# main_board.net
KiCad netlist of a schematic drawn in EAGLE
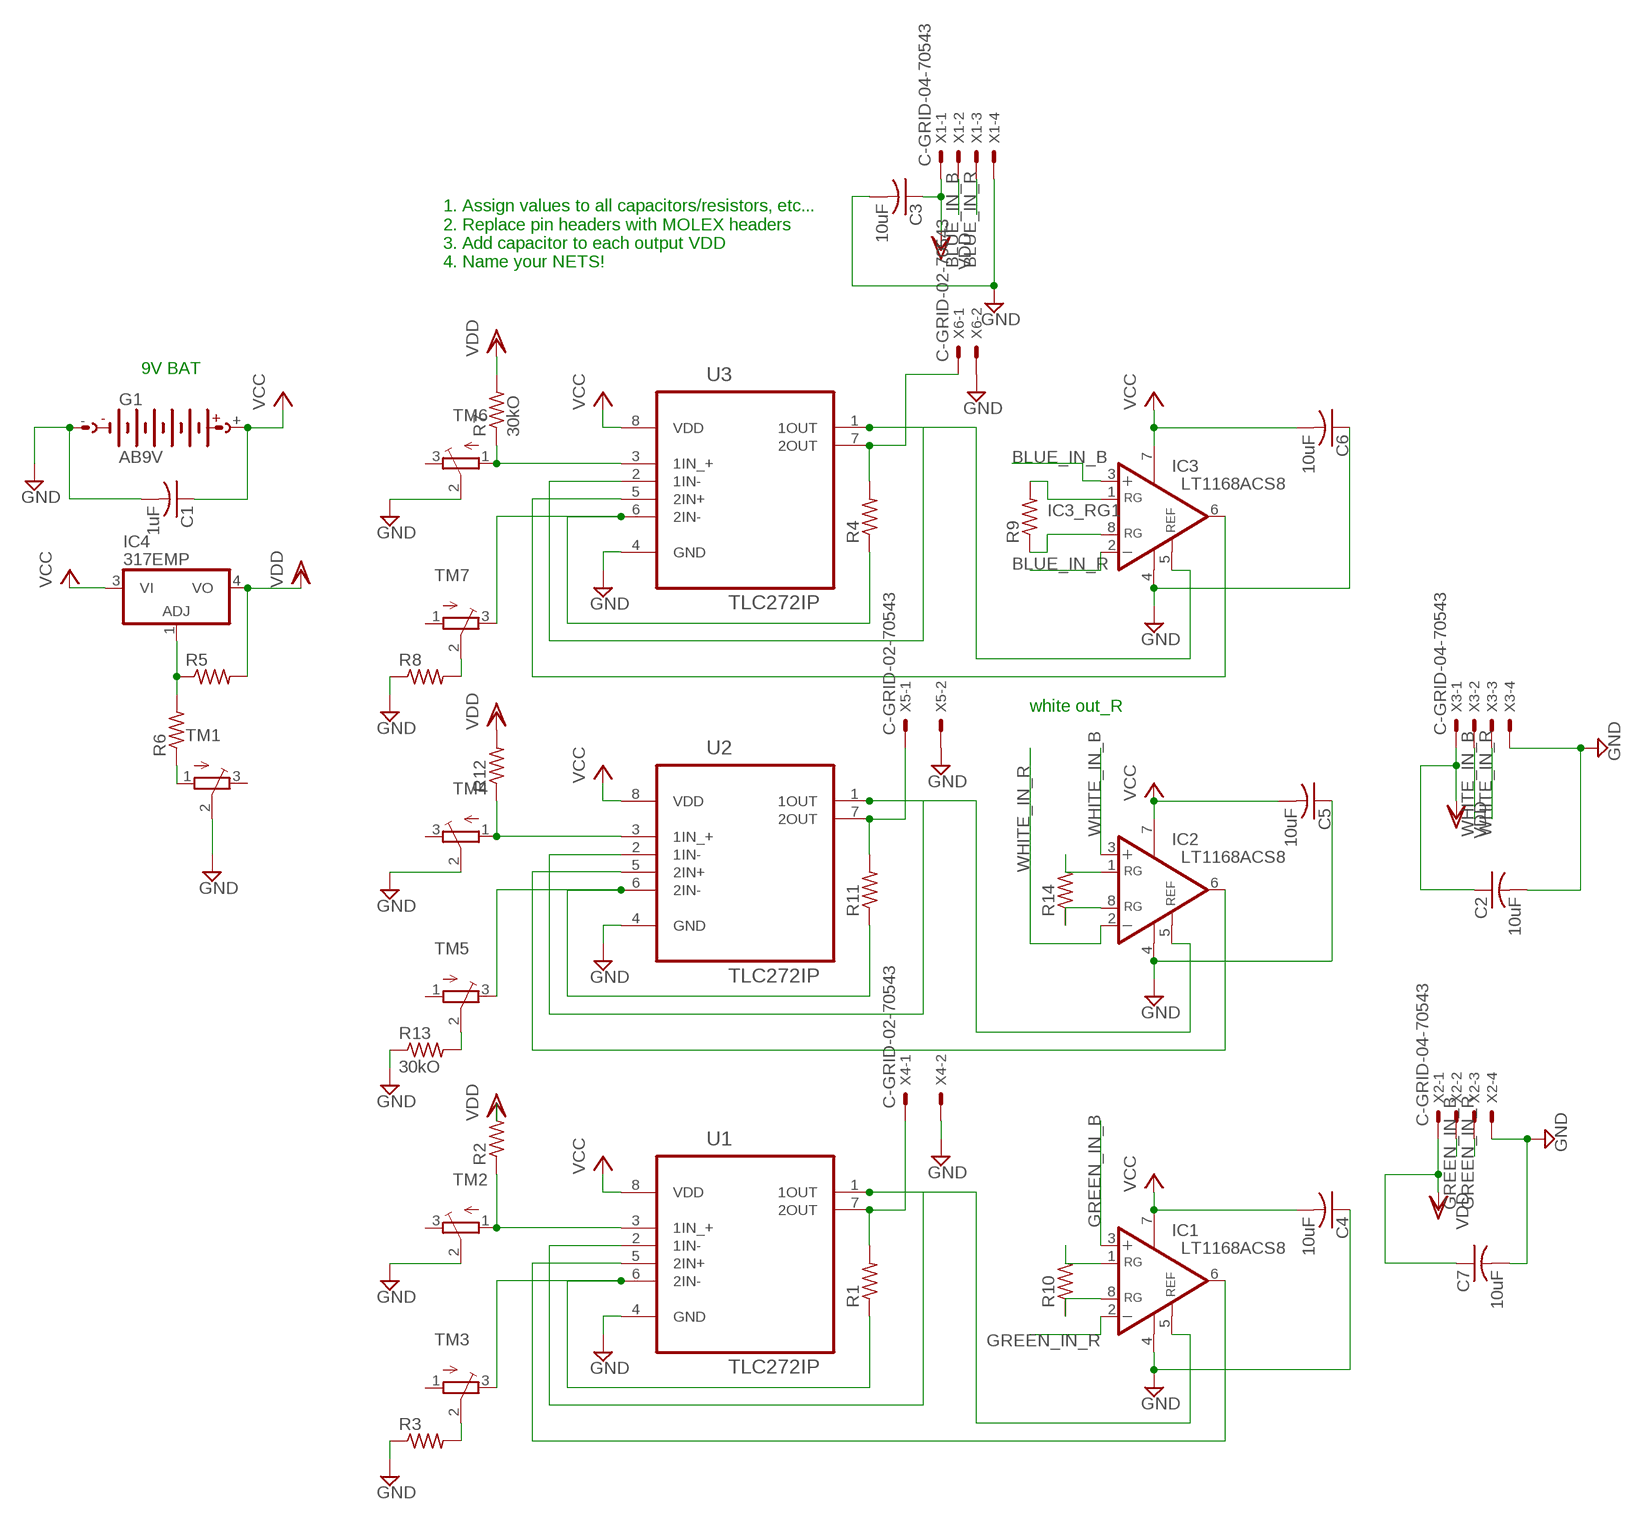
[diagram p0: schematic, sheet 1]

(export (version "E")
  (design (tool "Eeschema 10.0.6"))
  (components
    (comp (ref "C1")
      (value "1uF")
      (footprint "eagle-import:C2012")
      (libsource (lib "eagle-import") (part "C-USC2012"))
    )
    (comp (ref "C2")
      (value "10uF")
      (footprint "eagle-import:C2012")
      (libsource (lib "eagle-import") (part "C-USC2012"))
    )
    (comp (ref "C3")
      (value "10uF")
      (footprint "eagle-import:C2012")
      (libsource (lib "eagle-import") (part "C-USC2012"))
    )
    (comp (ref "C4")
      (value "10uF")
      (footprint "eagle-import:C2012")
      (libsource (lib "eagle-import") (part "C-USC2012"))
    )
    (comp (ref "C5")
      (value "10uF")
      (footprint "eagle-import:C2012")
      (libsource (lib "eagle-import") (part "C-USC2012"))
    )
    (comp (ref "C6")
      (value "10uF")
      (footprint "eagle-import:C2012")
      (libsource (lib "eagle-import") (part "C-USC2012"))
    )
    (comp (ref "C7")
      (value "10uF")
      (footprint "eagle-import:C2012")
      (libsource (lib "eagle-import") (part "C-USC2012"))
    )
    (comp (ref "G1")
      (value "AB9V")
      (footprint "eagle-import:AB9V")
      (libsource (lib "eagle-import") (part "AB9V"))
    )
    (comp (ref "IC1")
      (value "LT1168ACS8")
      (footprint "eagle-import:SOIC8")
      (libsource (lib "eagle-import") (part "LT1168S8AC"))
    )
    (comp (ref "IC2")
      (value "LT1168ACS8")
      (footprint "eagle-import:SOIC8")
      (libsource (lib "eagle-import") (part "LT1168S8AC"))
    )
    (comp (ref "IC3")
      (value "LT1168ACS8")
      (footprint "eagle-import:SOIC8")
      (libsource (lib "eagle-import") (part "LT1168S8AC"))
    )
    (comp (ref "IC4")
      (value "317EMP")
      (footprint "eagle-import:SOT223")
      (libsource (lib "eagle-import") (part "317EMP"))
    )
    (comp (ref "R1")
      (value "R-US_R1206")
      (footprint "eagle-import:R1206")
      (libsource (lib "eagle-import") (part "R-US_R1206"))
    )
    (comp (ref "R2")
      (value "R-US_R1206")
      (footprint "eagle-import:R1206")
      (libsource (lib "eagle-import") (part "R-US_R1206"))
    )
    (comp (ref "R3")
      (value "R-US_R1206")
      (footprint "eagle-import:R1206")
      (libsource (lib "eagle-import") (part "R-US_R1206"))
    )
    (comp (ref "R4")
      (value "R-US_R1206")
      (footprint "eagle-import:R1206")
      (libsource (lib "eagle-import") (part "R-US_R1206"))
    )
    (comp (ref "R5")
      (value "R-US_R1206")
      (footprint "eagle-import:R1206")
      (libsource (lib "eagle-import") (part "R-US_R1206"))
    )
    (comp (ref "R6")
      (value "R-US_R1206")
      (footprint "eagle-import:R1206")
      (libsource (lib "eagle-import") (part "R-US_R1206"))
    )
    (comp (ref "R7")
      (value "30kO")
      (footprint "eagle-import:R1206")
      (libsource (lib "eagle-import") (part "R-US_R1206"))
    )
    (comp (ref "R8")
      (value "R-US_R1206")
      (footprint "eagle-import:R1206")
      (libsource (lib "eagle-import") (part "R-US_R1206"))
    )
    (comp (ref "R9")
      (value "R-US_R1206")
      (footprint "eagle-import:R1206")
      (libsource (lib "eagle-import") (part "R-US_R1206"))
    )
    (comp (ref "R10")
      (value "R-US_R1206")
      (footprint "eagle-import:R1206")
      (libsource (lib "eagle-import") (part "R-US_R1206"))
    )
    (comp (ref "R11")
      (value "R-US_R1206")
      (footprint "eagle-import:R1206")
      (libsource (lib "eagle-import") (part "R-US_R1206"))
    )
    (comp (ref "R12")
      (value "R-US_R1206")
      (footprint "eagle-import:R1206")
      (libsource (lib "eagle-import") (part "R-US_R1206"))
    )
    (comp (ref "R13")
      (value "30kO")
      (footprint "eagle-import:R1206")
      (libsource (lib "eagle-import") (part "R-US_R1206"))
    )
    (comp (ref "R14")
      (value "R-US_R1206")
      (footprint "eagle-import:R1206")
      (libsource (lib "eagle-import") (part "R-US_R1206"))
    )
    (comp (ref "TM1")
      (value "TRIMPOT3386")
      (footprint "eagle-import:TRIM-3386")
      (libsource (lib "eagle-import") (part "TRIMPOT3386"))
    )
    (comp (ref "TM2")
      (value "TRIMPOT3386")
      (footprint "eagle-import:TRIM-3386")
      (libsource (lib "eagle-import") (part "TRIMPOT3386"))
    )
    (comp (ref "TM3")
      (value "TRIMPOT3386")
      (footprint "eagle-import:TRIM-3386")
      (libsource (lib "eagle-import") (part "TRIMPOT3386"))
    )
    (comp (ref "TM4")
      (value "TRIMPOT3386")
      (footprint "eagle-import:TRIM-3386")
      (libsource (lib "eagle-import") (part "TRIMPOT3386"))
    )
    (comp (ref "TM5")
      (value "TRIMPOT3386")
      (footprint "eagle-import:TRIM-3386")
      (libsource (lib "eagle-import") (part "TRIMPOT3386"))
    )
    (comp (ref "TM6")
      (value "TRIMPOT3386")
      (footprint "eagle-import:TRIM-3386")
      (libsource (lib "eagle-import") (part "TRIMPOT3386"))
    )
    (comp (ref "TM7")
      (value "TRIMPOT3386")
      (footprint "eagle-import:TRIM-3386")
      (libsource (lib "eagle-import") (part "TRIMPOT3386"))
    )
    (comp (ref "U1")
      (value "TLC272IP")
      (footprint "eagle-import:DIP254P762X508-8")
      (libsource (lib "eagle-import") (part "TLC272IP"))
    )
    (comp (ref "U2")
      (value "TLC272IP")
      (footprint "eagle-import:DIP254P762X508-8")
      (libsource (lib "eagle-import") (part "TLC272IP"))
    )
    (comp (ref "U3")
      (value "TLC272IP")
      (footprint "eagle-import:DIP254P762X508-8")
      (libsource (lib "eagle-import") (part "TLC272IP"))
    )
    (comp (ref "X1")
      (value "C-GRID-04-70543")
      (footprint "eagle-import:70543-04")
      (libsource (lib "eagle-import") (part "C-GRID-04-70543"))
    )
    (comp (ref "X2")
      (value "C-GRID-04-70543")
      (footprint "eagle-import:70543-04")
      (libsource (lib "eagle-import") (part "C-GRID-04-70543"))
    )
    (comp (ref "X3")
      (value "C-GRID-04-70543")
      (footprint "eagle-import:70543-04")
      (libsource (lib "eagle-import") (part "C-GRID-04-70543"))
    )
    (comp (ref "X4")
      (value "C-GRID-02-70543")
      (footprint "eagle-import:70543-02")
      (libsource (lib "eagle-import") (part "C-GRID-02-70543"))
    )
    (comp (ref "X5")
      (value "C-GRID-02-70543")
      (footprint "eagle-import:70543-02")
      (libsource (lib "eagle-import") (part "C-GRID-02-70543"))
    )
    (comp (ref "X6")
      (value "C-GRID-02-70543")
      (footprint "eagle-import:70543-02")
      (libsource (lib "eagle-import") (part "C-GRID-02-70543"))
    )
  )
  (nets
    (net (code "1") (name "/BLUE_IN_B") (class "Default")
      (node (ref "IC3") (pin "3") (pinfunction "+IN_3") (pintype "input"))
      (node (ref "X1") (pin "2") (pinfunction "S_2") (pintype "passive"))
    )
    (net (code "2") (name "/BLUE_IN_R") (class "Default")
      (node (ref "IC3") (pin "2") (pinfunction "-IN_2") (pintype "input"))
      (node (ref "X1") (pin "3") (pinfunction "S_3") (pintype "passive"))
    )
    (net (code "3") (name "/GREEN_IN_B") (class "Default")
      (node (ref "IC1") (pin "3") (pinfunction "+IN_3") (pintype "input"))
      (node (ref "X2") (pin "2") (pinfunction "S_2") (pintype "passive"))
    )
    (net (code "4") (name "/GREEN_IN_R") (class "Default")
      (node (ref "IC1") (pin "2") (pinfunction "-IN_2") (pintype "input"))
      (node (ref "X2") (pin "3") (pinfunction "S_3") (pintype "passive"))
    )
    (net (code "5") (name "/IC3_RG1") (class "Default")
      (node (ref "IC3") (pin "1") (pinfunction "RG_1") (pintype "input"))
      (node (ref "R9") (pin "2") (pinfunction "2_2") (pintype "passive"))
    )
    (net (code "6") (name "/WHITE_IN_B") (class "Default")
      (node (ref "IC2") (pin "3") (pinfunction "+IN_3") (pintype "input"))
      (node (ref "X3") (pin "2") (pinfunction "S_2") (pintype "passive"))
    )
    (net (code "7") (name "/WHITE_IN_R") (class "Default")
      (node (ref "IC2") (pin "2") (pinfunction "-IN_2") (pintype "input"))
      (node (ref "X3") (pin "3") (pinfunction "S_3") (pintype "passive"))
    )
    (net (code "8") (name "GND") (class "Default")
      (node (ref "C1") (pin "2") (pinfunction "2_2") (pintype "passive"))
      (node (ref "C2") (pin "2") (pinfunction "2_2") (pintype "passive"))
      (node (ref "C3") (pin "2") (pinfunction "2_2") (pintype "passive"))
      (node (ref "C4") (pin "1") (pinfunction "1_1") (pintype "passive"))
      (node (ref "C5") (pin "1") (pinfunction "1_1") (pintype "passive"))
      (node (ref "C6") (pin "1") (pinfunction "1_1") (pintype "passive"))
      (node (ref "C7") (pin "2") (pinfunction "2_2") (pintype "passive"))
      (node (ref "G1") (pin "-") (pinfunction "-_-") (pintype "passive"))
      (node (ref "IC1") (pin "4") (pinfunction "V-_4") (pintype "power_in"))
      (node (ref "IC2") (pin "4") (pinfunction "V-_4") (pintype "power_in"))
      (node (ref "IC3") (pin "4") (pinfunction "V-_4") (pintype "power_in"))
      (node (ref "R13") (pin "1") (pinfunction "1_1") (pintype "passive"))
      (node (ref "R3") (pin "1") (pinfunction "1_1") (pintype "passive"))
      (node (ref "R8") (pin "1") (pinfunction "1_1") (pintype "passive"))
      (node (ref "TM1") (pin "2") (pinfunction "S_2") (pintype "passive"))
      (node (ref "TM2") (pin "2") (pinfunction "S_2") (pintype "passive"))
      (node (ref "TM4") (pin "2") (pinfunction "S_2") (pintype "passive"))
      (node (ref "TM6") (pin "2") (pinfunction "S_2") (pintype "passive"))
      (node (ref "U1") (pin "4") (pinfunction "GND_4") (pintype "passive"))
      (node (ref "U2") (pin "4") (pinfunction "GND_4") (pintype "passive"))
      (node (ref "U3") (pin "4") (pinfunction "GND_4") (pintype "passive"))
      (node (ref "X1") (pin "4") (pinfunction "S_4") (pintype "passive"))
      (node (ref "X2") (pin "4") (pinfunction "S_4") (pintype "passive"))
      (node (ref "X3") (pin "4") (pinfunction "S_4") (pintype "passive"))
      (node (ref "X4") (pin "2") (pinfunction "S_2") (pintype "passive"))
      (node (ref "X5") (pin "2") (pinfunction "S_2") (pintype "passive"))
      (node (ref "X6") (pin "2") (pinfunction "S_2") (pintype "passive"))
    )
    (net (code "9") (name "Net-(IC1-OUT)") (class "Default")
      (node (ref "IC1") (pin "6") (pinfunction "OUT_6") (pintype "output"))
      (node (ref "U1") (pin "5") (pinfunction "2IN+_5") (pintype "input"))
    )
    (net (code "10") (name "Net-(IC1-REF)") (class "Default")
      (node (ref "IC1") (pin "5") (pinfunction "REF_5") (pintype "input"))
      (node (ref "U1") (pin "1") (pinfunction "1OUT_1") (pintype "output"))
      (node (ref "U1") (pin "2") (pinfunction "1IN-_2") (pintype "input"))
    )
    (net (code "11") (name "Net-(IC1-RG-Pad1)") (class "Default")
      (node (ref "IC1") (pin "1") (pinfunction "RG_1") (pintype "input"))
      (node (ref "R10") (pin "2") (pinfunction "2_2") (pintype "passive"))
    )
    (net (code "12") (name "Net-(IC1-RG-Pad8)") (class "Default")
      (node (ref "IC1") (pin "8") (pinfunction "RG_8") (pintype "input"))
      (node (ref "R10") (pin "1") (pinfunction "1_1") (pintype "passive"))
    )
    (net (code "13") (name "Net-(IC2-OUT)") (class "Default")
      (node (ref "IC2") (pin "6") (pinfunction "OUT_6") (pintype "output"))
      (node (ref "U2") (pin "5") (pinfunction "2IN+_5") (pintype "input"))
    )
    (net (code "14") (name "Net-(IC2-REF)") (class "Default")
      (node (ref "IC2") (pin "5") (pinfunction "REF_5") (pintype "input"))
      (node (ref "U2") (pin "1") (pinfunction "1OUT_1") (pintype "output"))
      (node (ref "U2") (pin "2") (pinfunction "1IN-_2") (pintype "input"))
    )
    (net (code "15") (name "Net-(IC2-RG-Pad1)") (class "Default")
      (node (ref "IC2") (pin "1") (pinfunction "RG_1") (pintype "input"))
      (node (ref "R14") (pin "2") (pinfunction "2_2") (pintype "passive"))
    )
    (net (code "16") (name "Net-(IC2-RG-Pad8)") (class "Default")
      (node (ref "IC2") (pin "8") (pinfunction "RG_8") (pintype "input"))
      (node (ref "R14") (pin "1") (pinfunction "1_1") (pintype "passive"))
    )
    (net (code "17") (name "Net-(IC3-OUT)") (class "Default")
      (node (ref "IC3") (pin "6") (pinfunction "OUT_6") (pintype "output"))
      (node (ref "U3") (pin "5") (pinfunction "2IN+_5") (pintype "input"))
    )
    (net (code "18") (name "Net-(IC3-REF)") (class "Default")
      (node (ref "IC3") (pin "5") (pinfunction "REF_5") (pintype "input"))
      (node (ref "U3") (pin "1") (pinfunction "1OUT_1") (pintype "output"))
      (node (ref "U3") (pin "2") (pinfunction "1IN-_2") (pintype "input"))
    )
    (net (code "19") (name "Net-(IC3-RG-Pad8)") (class "Default")
      (node (ref "IC3") (pin "8") (pinfunction "RG_8") (pintype "input"))
      (node (ref "R9") (pin "1") (pinfunction "1_1") (pintype "passive"))
    )
    (net (code "20") (name "Net-(IC4-ADJ)") (class "Default")
      (node (ref "IC4") (pin "1") (pinfunction "ADJ_1") (pintype "input"))
      (node (ref "R5") (pin "1") (pinfunction "1_1") (pintype "passive"))
      (node (ref "R6") (pin "2") (pinfunction "2_2") (pintype "passive"))
    )
    (net (code "21") (name "Net-(TM1-A)") (class "Default")
      (node (ref "R6") (pin "1") (pinfunction "1_1") (pintype "passive"))
      (node (ref "TM1") (pin "1") (pinfunction "A_1") (pintype "passive"))
    )
    (net (code "22") (name "Net-(TM2-A)") (class "Default")
      (node (ref "R2") (pin "1") (pinfunction "1_1") (pintype "passive"))
      (node (ref "TM2") (pin "1") (pinfunction "A_1") (pintype "passive"))
      (node (ref "U1") (pin "3") (pinfunction "1IN_+_3") (pintype "input"))
    )
    (net (code "23") (name "Net-(TM3-E)") (class "Default")
      (node (ref "R1") (pin "1") (pinfunction "1_1") (pintype "passive"))
      (node (ref "TM3") (pin "3") (pinfunction "E_3") (pintype "passive"))
      (node (ref "U1") (pin "6") (pinfunction "2IN-_6") (pintype "input"))
    )
    (net (code "24") (name "Net-(TM3-S)") (class "Default")
      (node (ref "R3") (pin "2") (pinfunction "2_2") (pintype "passive"))
      (node (ref "TM3") (pin "2") (pinfunction "S_2") (pintype "passive"))
    )
    (net (code "25") (name "Net-(TM4-A)") (class "Default")
      (node (ref "R12") (pin "1") (pinfunction "1_1") (pintype "passive"))
      (node (ref "TM4") (pin "1") (pinfunction "A_1") (pintype "passive"))
      (node (ref "U2") (pin "3") (pinfunction "1IN_+_3") (pintype "input"))
    )
    (net (code "26") (name "Net-(TM5-E)") (class "Default")
      (node (ref "R11") (pin "1") (pinfunction "1_1") (pintype "passive"))
      (node (ref "TM5") (pin "3") (pinfunction "E_3") (pintype "passive"))
      (node (ref "U2") (pin "6") (pinfunction "2IN-_6") (pintype "input"))
    )
    (net (code "27") (name "Net-(TM5-S)") (class "Default")
      (node (ref "R13") (pin "2") (pinfunction "2_2") (pintype "passive"))
      (node (ref "TM5") (pin "2") (pinfunction "S_2") (pintype "passive"))
    )
    (net (code "28") (name "Net-(TM6-A)") (class "Default")
      (node (ref "R7") (pin "1") (pinfunction "1_1") (pintype "passive"))
      (node (ref "TM6") (pin "1") (pinfunction "A_1") (pintype "passive"))
      (node (ref "U3") (pin "3") (pinfunction "1IN_+_3") (pintype "input"))
    )
    (net (code "29") (name "Net-(TM7-E)") (class "Default")
      (node (ref "R4") (pin "1") (pinfunction "1_1") (pintype "passive"))
      (node (ref "TM7") (pin "3") (pinfunction "E_3") (pintype "passive"))
      (node (ref "U3") (pin "6") (pinfunction "2IN-_6") (pintype "input"))
    )
    (net (code "30") (name "Net-(TM7-S)") (class "Default")
      (node (ref "R8") (pin "2") (pinfunction "2_2") (pintype "passive"))
      (node (ref "TM7") (pin "2") (pinfunction "S_2") (pintype "passive"))
    )
    (net (code "31") (name "Net-(U1-2OUT)") (class "Default")
      (node (ref "R1") (pin "2") (pinfunction "2_2") (pintype "passive"))
      (node (ref "U1") (pin "7") (pinfunction "2OUT_7") (pintype "output"))
      (node (ref "X4") (pin "1") (pinfunction "S_1") (pintype "passive"))
    )
    (net (code "32") (name "Net-(U2-2OUT)") (class "Default")
      (node (ref "R11") (pin "2") (pinfunction "2_2") (pintype "passive"))
      (node (ref "U2") (pin "7") (pinfunction "2OUT_7") (pintype "output"))
      (node (ref "X5") (pin "1") (pinfunction "S_1") (pintype "passive"))
    )
    (net (code "33") (name "Net-(U3-2OUT)") (class "Default")
      (node (ref "R4") (pin "2") (pinfunction "2_2") (pintype "passive"))
      (node (ref "U3") (pin "7") (pinfunction "2OUT_7") (pintype "output"))
      (node (ref "X6") (pin "1") (pinfunction "S_1") (pintype "passive"))
    )
    (net (code "34") (name "VCC") (class "Default")
      (node (ref "C1") (pin "1") (pinfunction "1_1") (pintype "passive"))
      (node (ref "C4") (pin "2") (pinfunction "2_2") (pintype "passive"))
      (node (ref "C5") (pin "2") (pinfunction "2_2") (pintype "passive"))
      (node (ref "C6") (pin "2") (pinfunction "2_2") (pintype "passive"))
      (node (ref "G1") (pin "+") (pinfunction "+_+") (pintype "passive"))
      (node (ref "IC1") (pin "7") (pinfunction "V+_7") (pintype "power_in"))
      (node (ref "IC2") (pin "7") (pinfunction "V+_7") (pintype "power_in"))
      (node (ref "IC3") (pin "7") (pinfunction "V+_7") (pintype "power_in"))
      (node (ref "IC4") (pin "3") (pinfunction "VI_3") (pintype "input"))
      (node (ref "U1") (pin "8") (pinfunction "VDD_8") (pintype "power_in"))
      (node (ref "U2") (pin "8") (pinfunction "VDD_8") (pintype "power_in"))
      (node (ref "U3") (pin "8") (pinfunction "VDD_8") (pintype "power_in"))
    )
    (net (code "35") (name "VDD") (class "Default")
      (node (ref "C2") (pin "1") (pinfunction "1_1") (pintype "passive"))
      (node (ref "C3") (pin "1") (pinfunction "1_1") (pintype "passive"))
      (node (ref "C7") (pin "1") (pinfunction "1_1") (pintype "passive"))
      (node (ref "IC4") (pin "4") (pinfunction "VO_4") (pintype "passive"))
      (node (ref "R12") (pin "2") (pinfunction "2_2") (pintype "passive"))
      (node (ref "R2") (pin "2") (pinfunction "2_2") (pintype "passive"))
      (node (ref "R5") (pin "2") (pinfunction "2_2") (pintype "passive"))
      (node (ref "R7") (pin "2") (pinfunction "2_2") (pintype "passive"))
      (node (ref "X1") (pin "1") (pinfunction "S_1") (pintype "passive"))
      (node (ref "X2") (pin "1") (pinfunction "S_1") (pintype "passive"))
      (node (ref "X3") (pin "1") (pinfunction "S_1") (pintype "passive"))
    )
    (net (code "36") (name "unconnected-(TM1-E-Pad3)") (class "Default")
      (node (ref "TM1") (pin "3") (pinfunction "E_3") (pintype "passive"))
    )
    (net (code "37") (name "unconnected-(TM2-E-Pad3)") (class "Default")
      (node (ref "TM2") (pin "3") (pinfunction "E_3") (pintype "passive"))
    )
    (net (code "38") (name "unconnected-(TM3-A-Pad1)") (class "Default")
      (node (ref "TM3") (pin "1") (pinfunction "A_1") (pintype "passive"))
    )
    (net (code "39") (name "unconnected-(TM4-E-Pad3)") (class "Default")
      (node (ref "TM4") (pin "3") (pinfunction "E_3") (pintype "passive"))
    )
    (net (code "40") (name "unconnected-(TM5-A-Pad1)") (class "Default")
      (node (ref "TM5") (pin "1") (pinfunction "A_1") (pintype "passive"))
    )
    (net (code "41") (name "unconnected-(TM6-E-Pad3)") (class "Default")
      (node (ref "TM6") (pin "3") (pinfunction "E_3") (pintype "passive"))
    )
    (net (code "42") (name "unconnected-(TM7-A-Pad1)") (class "Default")
      (node (ref "TM7") (pin "1") (pinfunction "A_1") (pintype "passive"))
    )
  )
)
